# P03_BCS1_USB_Serial_uSD.net
KiCad netlist of a schematic drawn in Altium Designer
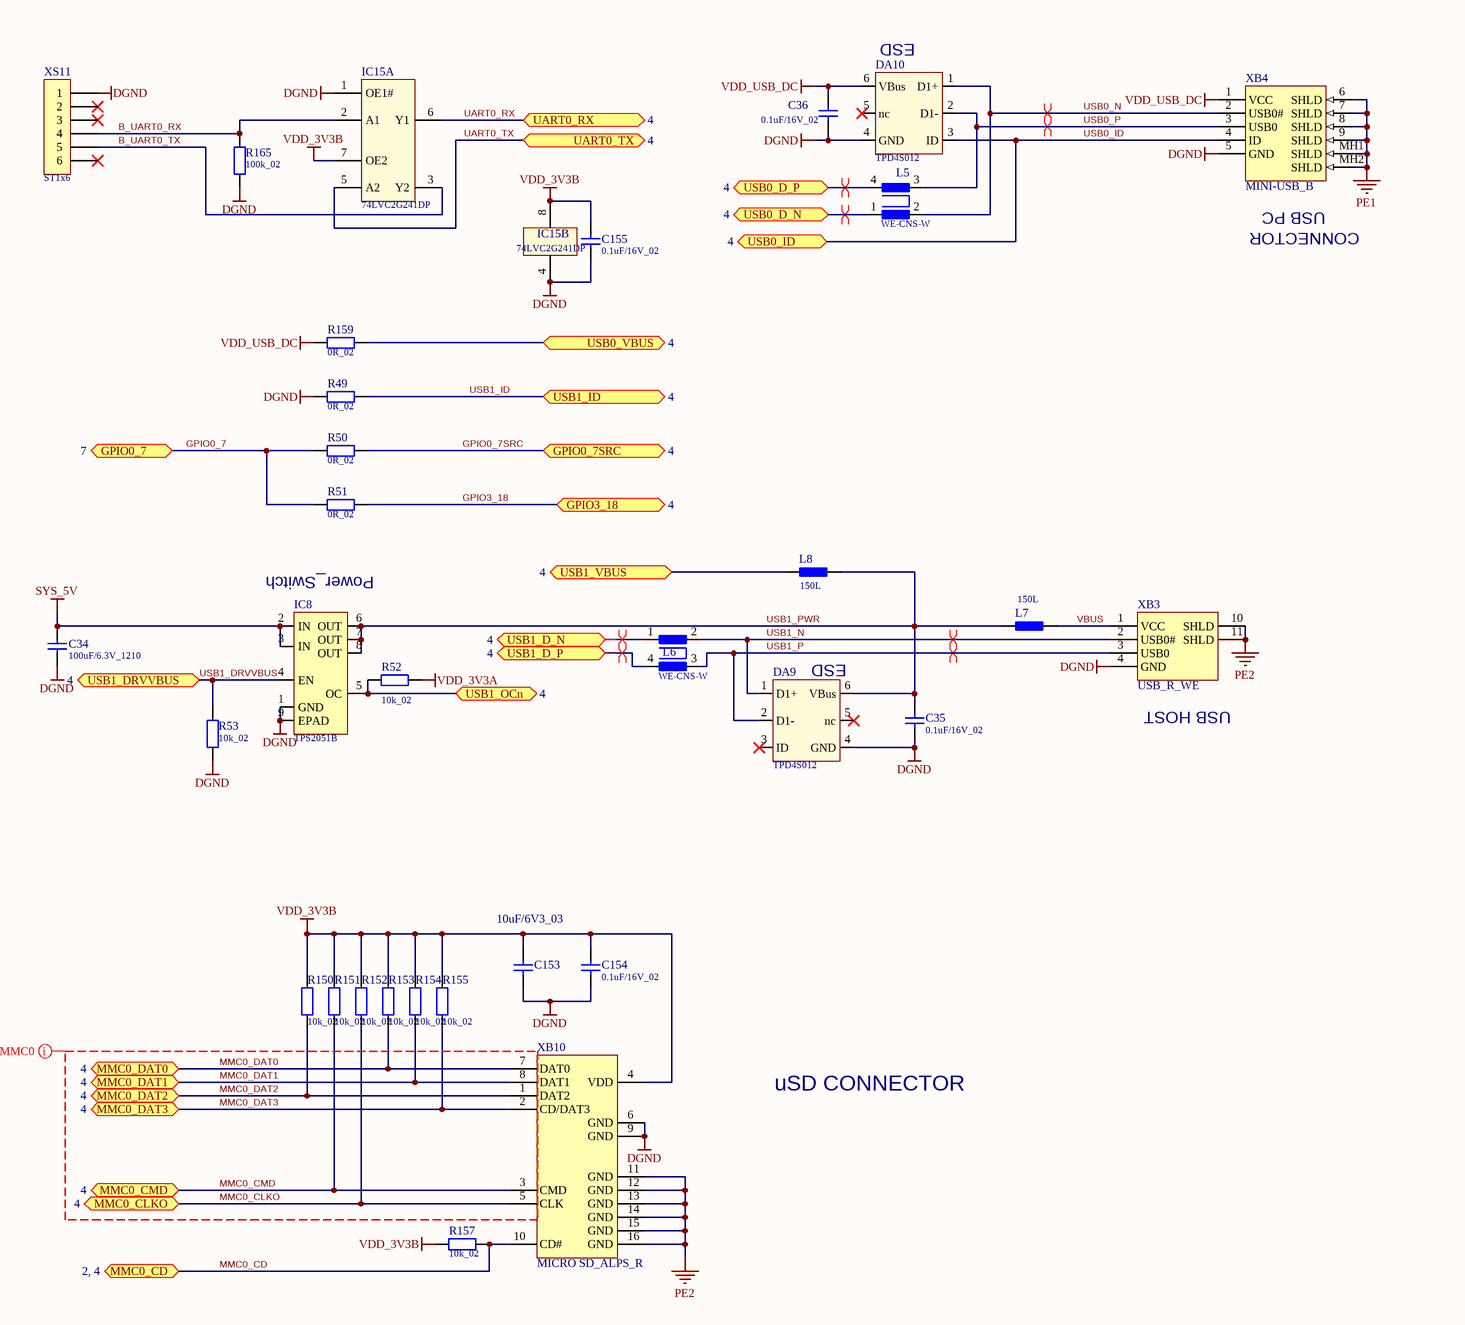
[diagram p0: P03_BCS1_USB, Serial, uSD.SchDoc]

(export (version "E")
  (design (tool "Eeschema 10.0.6"))
  (components
    (comp (ref "C34")
      (value "100uF/6.3V_1210")
      (footprint "CC3225-1210")
      (description "Capacitor 1210; 6.3V")
      (libsource (lib "*") (part "C100uF/6.3V_10"))
    )
    (comp (ref "C35")
      (value "0.1uF/16V_02")
      (footprint "CC1005-0402")
      (description "Capacitor 0402 16V Y5V")
      (libsource (lib "*") (part "C0.1uF/16V_02"))
    )
    (comp (ref "C36")
      (value "0.1uF/16V_02")
      (footprint "CC1005-0402")
      (description "Capacitor 0402 16V Y5V")
      (libsource (lib "*") (part "C0.1uF/16V_02"))
    )
    (comp (ref "C153")
      (value "10uF/6V3_03")
      (footprint "CC1608-0603")
      (description "Capacitor 0603 6V3; 10%, X5R")
      (libsource (lib "*") (part "C10uF/6V3_03"))
    )
    (comp (ref "C154")
      (value "0.1uF/16V_02")
      (footprint "CC1005-0402")
      (description "Capacitor 0402 16V Y5V")
      (libsource (lib "*") (part "C0.1uF/16V_02"))
    )
    (comp (ref "C155")
      (value "0.1uF/16V_02")
      (footprint "CC1005-0402")
      (description "Capacitor 0402 16V Y5V")
      (libsource (lib "*") (part "C0.1uF/16V_02"))
    )
    (comp (ref "DA9")
      (value "TPD4S012")
      (footprint "SON6")
      (description "Diode Array TVS,  for USB2.0 TypB; 4fach")
      (libsource (lib "*") (part "DATPD4S012"))
    )
    (comp (ref "DA10")
      (value "TPD4S012")
      (footprint "SON6")
      (description "Diode Array TVS,  for USB2.0 TypB; 4fach")
      (libsource (lib "") (part "DATPD4S012_1"))
    )
    (comp (ref "IC8")
      (value "TPS2051B")
      (footprint "DGN-MSOP8+1")
      (description "Current-Limited PowerSwitch")
      (libsource (lib "*") (part "ICTPS2051B"))
    )
    (comp (ref "IC15")
      (value "74LVC2G241DP")
      (footprint "TSSOP8 - 3x3")
      (description "dual buffer/line driver; 3-state, 5V-tolerant")
      (libsource (lib "*") (part "IC74LVC2G241DP"))
    )
    (comp (ref "L5")
      (value "WE-CNS-W")
      (footprint "WE-CNS_W - 0805")
      (description "Stromkomp. Datenleitungsfilter WE-CNS-W, 90 Ohm")
      (libsource (lib "*") (part "LWE-CNS FILTER"))
    )
    (comp (ref "L6")
      (value "WE-CNS-W")
      (footprint "WE-CNS_W - 0805")
      (description "Stromkomp. Datenleitungsfilter WE-CNS-W, 90 Ohm")
      (libsource (lib "*") (part "LWE-CNS FILTER"))
    )
    (comp (ref "L7")
      (value "150L")
      (footprint "CR2012-0805")
      (description "Inductor 120 Ohm Ferrite 0805, 800mA")
      (libsource (lib "*") (part "L150 Ohm Ferrite"))
    )
    (comp (ref "L8")
      (value "150L")
      (footprint "CR2012-0805")
      (description "Inductor 120 Ohm Ferrite 0805, 800mA")
      (libsource (lib "*") (part "L150 Ohm Ferrite"))
    )
    (comp (ref "R49")
      (value "0R_02")
      (footprint "CR1005-0402")
      (description "Resistor 0402")
      (libsource (lib "*") (part "R0R_02"))
    )
    (comp (ref "R50")
      (value "0R_02")
      (footprint "CR1005-0402")
      (description "Resistor 0402")
      (libsource (lib "*") (part "R0R_02"))
    )
    (comp (ref "R51")
      (value "0R_02")
      (footprint "CR1005-0402")
      (description "Resistor 0402")
      (libsource (lib "*") (part "R0R_02"))
    )
    (comp (ref "R52")
      (value "10k_02")
      (footprint "CR1005-0402")
      (description "Resistor 0402")
      (libsource (lib "") (part "R10k_02_1"))
    )
    (comp (ref "R53")
      (value "10k_02")
      (footprint "CR1005-0402")
      (description "Resistor 0402")
      (libsource (lib "") (part "R10k_02_2"))
    )
    (comp (ref "R150")
      (value "10k_02")
      (footprint "CR1005-0402")
      (description "Resistor 0402")
      (libsource (lib "*") (part "R10k_02"))
    )
    (comp (ref "R151")
      (value "10k_02")
      (footprint "CR1005-0402")
      (description "Resistor 0402")
      (libsource (lib "*") (part "R10k_02"))
    )
    (comp (ref "R152")
      (value "10k_02")
      (footprint "CR1005-0402")
      (description "Resistor 0402")
      (libsource (lib "*") (part "R10k_02"))
    )
    (comp (ref "R153")
      (value "10k_02")
      (footprint "CR1005-0402")
      (description "Resistor 0402")
      (libsource (lib "*") (part "R10k_02"))
    )
    (comp (ref "R154")
      (value "10k_02")
      (footprint "CR1005-0402")
      (description "Resistor 0402")
      (libsource (lib "*") (part "R10k_02"))
    )
    (comp (ref "R155")
      (value "10k_02")
      (footprint "CR1005-0402")
      (description "Resistor 0402")
      (libsource (lib "*") (part "R10k_02"))
    )
    (comp (ref "R157")
      (value "10k_02")
      (footprint "CR1005-0402")
      (description "Resistor 0402")
      (libsource (lib "") (part "R10k_02_1"))
    )
    (comp (ref "R159")
      (value "0R_02")
      (footprint "CR1005-0402")
      (description "Resistor 0402")
      (libsource (lib "*") (part "R0R_02"))
    )
    (comp (ref "R165")
      (value "100k_02")
      (footprint "CR1005-0402")
      (description "Resistor 0402")
      (libsource (lib "*") (part "R100k_02"))
    )
    (comp (ref "XB3")
      (value "USB_R_WE")
      (footprint "61400416021")
      (description "USB einfach RA Type A")
      (libsource (lib "*") (part "XBUSB_R_WE"))
    )
    (comp (ref "XB4")
      (value "MINI-USB_B")
      (footprint "USB-MINI-B")
      (description "USB MINI Typ B einfach 5pol.")
      (libsource (lib "*") (part "XBUSB_Mini-B"))
    )
    (comp (ref "XB10")
      (value "MICRO SD_ALPS_R")
      (footprint "Micro-SD-Card-Conn-ALPS- Reverse Mount")
      (description "MICRO SD Memory card connector push/push  reverse mount ALPS (SCHA5B0200)")
      (libsource (lib "*") (part "XBMICRO_SD_ALPS_R"))
    )
    (comp (ref "XS11")
      (value "ST1x6")
      (footprint "ST6")
      (description "Modul-Stiftleiste 2.54mm pitch einreihig, 6pol.")
      (libsource (lib "*") (part "XST1X6"))
    )
  )
  (nets
    (net (code "1") (name "/B_UART0_RX") (class "Default")
      (node (ref "IC15") (pin "2") (pinfunction "A1_2") (pintype "passive"))
      (node (ref "R165") (pin "2") (pinfunction "2_2") (pintype "passive"))
      (node (ref "XS11") (pin "4") (pinfunction "4_4") (pintype "passive"))
    )
    (net (code "2") (name "/B_UART0_TX") (class "Default")
      (node (ref "IC15") (pin "3") (pinfunction "Y2_3") (pintype "passive"))
      (node (ref "XS11") (pin "5") (pinfunction "5_5") (pintype "passive"))
    )
    (net (code "3") (name "/GPIO0_7") (class "Default")
      (node (ref "R50") (pin "1") (pinfunction "1_1") (pintype "passive"))
      (node (ref "R51") (pin "1") (pinfunction "1_1") (pintype "passive"))
    )
    (net (code "4") (name "/GPIO0_7SRC") (class "Default")
      (node (ref "R50") (pin "2") (pinfunction "2_2") (pintype "passive"))
    )
    (net (code "5") (name "/GPIO3_18") (class "Default")
      (node (ref "R51") (pin "2") (pinfunction "2_2") (pintype "passive"))
    )
    (net (code "6") (name "/MMC0_CD") (class "Default")
      (node (ref "R157") (pin "2") (pinfunction "2_2") (pintype "passive"))
      (node (ref "XB10") (pin "10") (pinfunction "CD#_10") (pintype "passive"))
    )
    (net (code "7") (name "/MMC0_CLKO") (class "Default")
      (node (ref "R152") (pin "2") (pinfunction "2_2") (pintype "passive"))
      (node (ref "XB10") (pin "5") (pinfunction "CLK_5") (pintype "passive"))
    )
    (net (code "8") (name "/MMC0_CMD") (class "Default")
      (node (ref "R151") (pin "2") (pinfunction "2_2") (pintype "passive"))
      (node (ref "XB10") (pin "3") (pinfunction "CMD_3") (pintype "passive"))
    )
    (net (code "9") (name "/MMC0_DAT0") (class "Default")
      (node (ref "R153") (pin "2") (pinfunction "2_2") (pintype "passive"))
      (node (ref "XB10") (pin "7") (pinfunction "DAT0_7") (pintype "passive"))
    )
    (net (code "10") (name "/MMC0_DAT1") (class "Default")
      (node (ref "R154") (pin "2") (pinfunction "2_2") (pintype "passive"))
      (node (ref "XB10") (pin "8") (pinfunction "DAT1_8") (pintype "passive"))
    )
    (net (code "11") (name "/MMC0_DAT2") (class "Default")
      (node (ref "R150") (pin "2") (pinfunction "2_2") (pintype "passive"))
      (node (ref "XB10") (pin "1") (pinfunction "DAT2_1") (pintype "passive"))
    )
    (net (code "12") (name "/MMC0_DAT3") (class "Default")
      (node (ref "R155") (pin "2") (pinfunction "2_2") (pintype "passive"))
      (node (ref "XB10") (pin "2") (pinfunction "CD/DAT3_2") (pintype "passive"))
    )
    (net (code "13") (name "/UART0_RX") (class "Default")
      (node (ref "IC15") (pin "6") (pinfunction "Y1_6") (pintype "passive"))
    )
    (net (code "14") (name "/UART0_TX") (class "Default")
      (node (ref "IC15") (pin "5") (pinfunction "A2_5") (pintype "passive"))
    )
    (net (code "15") (name "/USB0_D_N") (class "Default")
      (node (ref "L5") (pin "1") (pinfunction "1_1") (pintype "passive"))
    )
    (net (code "16") (name "/USB0_D_P") (class "Default")
      (node (ref "L5") (pin "4") (pinfunction "4_4") (pintype "passive"))
    )
    (net (code "17") (name "/USB0_ID") (class "Default")
      (node (ref "DA10") (pin "3") (pinfunction "ID_3") (pintype "passive"))
      (node (ref "XB4") (pin "4") (pinfunction "ID_4") (pintype "passive"))
    )
    (net (code "18") (name "/USB0_N") (class "Default")
      (node (ref "DA10") (pin "1") (pinfunction "D1+_1") (pintype "passive"))
      (node (ref "L5") (pin "2") (pinfunction "2_2") (pintype "passive"))
      (node (ref "XB4") (pin "2") (pinfunction "USB0#_2") (pintype "passive"))
    )
    (net (code "19") (name "/USB0_P") (class "Default")
      (node (ref "DA10") (pin "2") (pinfunction "D1-_2") (pintype "passive"))
      (node (ref "L5") (pin "3") (pinfunction "3_3") (pintype "passive"))
      (node (ref "XB4") (pin "3") (pinfunction "USB0_3") (pintype "passive"))
    )
    (net (code "20") (name "/USB0_VBUS") (class "Default")
      (node (ref "R159") (pin "2") (pinfunction "2_2") (pintype "passive"))
    )
    (net (code "21") (name "/USB1_DRVVBUS") (class "Default")
      (node (ref "IC8") (pin "4") (pinfunction "EN_4") (pintype "passive"))
      (node (ref "R53") (pin "2") (pinfunction "2_2") (pintype "passive"))
    )
    (net (code "22") (name "/USB1_D_N") (class "Default")
      (node (ref "L6") (pin "1") (pinfunction "1_1") (pintype "passive"))
    )
    (net (code "23") (name "/USB1_D_P") (class "Default")
      (node (ref "L6") (pin "4") (pinfunction "4_4") (pintype "passive"))
    )
    (net (code "24") (name "/USB1_ID") (class "Default")
      (node (ref "R49") (pin "2") (pinfunction "2_2") (pintype "passive"))
    )
    (net (code "25") (name "/USB1_N") (class "Default")
      (node (ref "DA9") (pin "1") (pinfunction "D1+_1") (pintype "passive"))
      (node (ref "L6") (pin "2") (pinfunction "2_2") (pintype "passive"))
      (node (ref "XB3") (pin "2") (pinfunction "USB0#_2") (pintype "passive"))
    )
    (net (code "26") (name "/USB1_OCn") (class "Default")
      (node (ref "IC8") (pin "5") (pinfunction "OC_5") (pintype "power_in"))
      (node (ref "R52") (pin "1") (pinfunction "1_1") (pintype "passive"))
    )
    (net (code "27") (name "/USB1_P") (class "Default")
      (node (ref "DA9") (pin "2") (pinfunction "D1-_2") (pintype "passive"))
      (node (ref "L6") (pin "3") (pinfunction "3_3") (pintype "passive"))
      (node (ref "XB3") (pin "3") (pinfunction "USB0_3") (pintype "passive"))
    )
    (net (code "28") (name "/USB1_PWR") (class "Default")
      (node (ref "C35") (pin "1") (pinfunction "1_1") (pintype "passive"))
      (node (ref "DA9") (pin "6") (pinfunction "VBus_6") (pintype "passive"))
      (node (ref "IC8") (pin "6") (pinfunction "OUT_6") (pintype "passive"))
      (node (ref "IC8") (pin "7") (pinfunction "OUT_7") (pintype "passive"))
      (node (ref "IC8") (pin "8") (pinfunction "OUT_8") (pintype "passive"))
      (node (ref "L7") (pin "1") (pinfunction "1_1") (pintype "passive"))
      (node (ref "L8") (pin "2") (pinfunction "2_2") (pintype "passive"))
    )
    (net (code "29") (name "/USB1_VBUS") (class "Default")
      (node (ref "L8") (pin "1") (pinfunction "1_1") (pintype "passive"))
    )
    (net (code "30") (name "/VBUS") (class "Default")
      (node (ref "L7") (pin "2") (pinfunction "2_2") (pintype "passive"))
      (node (ref "XB3") (pin "1") (pinfunction "VCC_1") (pintype "passive"))
    )
    (net (code "31") (name "DGND") (class "Default")
      (node (ref "C153") (pin "1") (pinfunction "1_1") (pintype "passive"))
      (node (ref "C154") (pin "1") (pinfunction "1_1") (pintype "passive"))
      (node (ref "C155") (pin "2") (pinfunction "2_2") (pintype "passive"))
      (node (ref "C34") (pin "1") (pinfunction "1_1") (pintype "passive"))
      (node (ref "C35") (pin "2") (pinfunction "2_2") (pintype "passive"))
      (node (ref "C36") (pin "2") (pinfunction "2_2") (pintype "passive"))
      (node (ref "DA10") (pin "4") (pinfunction "GND_4") (pintype "passive"))
      (node (ref "DA9") (pin "4") (pinfunction "GND_4") (pintype "passive"))
      (node (ref "IC15") (pin "1") (pinfunction "OE1#_1") (pintype "passive"))
      (node (ref "IC15") (pin "4") (pinfunction "GND_4") (pintype "passive"))
      (node (ref "IC8") (pin "1") (pinfunction "GND_1") (pintype "passive"))
      (node (ref "IC8") (pin "9") (pinfunction "EPAD_9") (pintype "passive"))
      (node (ref "R165") (pin "1") (pinfunction "1_1") (pintype "passive"))
      (node (ref "R49") (pin "1") (pinfunction "1_1") (pintype "passive"))
      (node (ref "R53") (pin "1") (pinfunction "1_1") (pintype "passive"))
      (node (ref "XB10") (pin "6") (pinfunction "GND_6") (pintype "passive"))
      (node (ref "XB10") (pin "9") (pinfunction "GND_9") (pintype "passive"))
      (node (ref "XB3") (pin "4") (pinfunction "GND_4") (pintype "passive"))
      (node (ref "XB4") (pin "5") (pinfunction "GND_5") (pintype "passive"))
      (node (ref "XS11") (pin "1") (pinfunction "1_1") (pintype "passive"))
    )
    (net (code "32") (name "PE1") (class "Default")
      (node (ref "XB4") (pin "6") (pinfunction "SHLD_6") (pintype "input"))
      (node (ref "XB4") (pin "7") (pinfunction "SHLD_7") (pintype "input"))
      (node (ref "XB4") (pin "8") (pinfunction "SHLD_8") (pintype "input"))
      (node (ref "XB4") (pin "9") (pinfunction "SHLD_9") (pintype "input"))
      (node (ref "XB4") (pin "MH1") (pinfunction "SHLD_MH1") (pintype "input"))
      (node (ref "XB4") (pin "MH2") (pinfunction "SHLD_MH2") (pintype "input"))
    )
    (net (code "33") (name "PE2") (class "Default")
      (node (ref "XB10") (pin "11") (pinfunction "GND_11") (pintype "passive"))
      (node (ref "XB10") (pin "12") (pinfunction "GND_12") (pintype "passive"))
      (node (ref "XB10") (pin "13") (pinfunction "GND_13") (pintype "passive"))
      (node (ref "XB10") (pin "14") (pinfunction "GND_14") (pintype "passive"))
      (node (ref "XB10") (pin "15") (pinfunction "GND_15") (pintype "passive"))
      (node (ref "XB10") (pin "16") (pinfunction "GND_16") (pintype "passive"))
      (node (ref "XB3") (pin "10") (pinfunction "SHLD_10") (pintype "passive"))
      (node (ref "XB3") (pin "11") (pinfunction "SHLD_11") (pintype "passive"))
    )
    (net (code "34") (name "SYS_5V") (class "Default")
      (node (ref "C34") (pin "2") (pinfunction "2_2") (pintype "passive"))
      (node (ref "IC8") (pin "2") (pinfunction "IN_2") (pintype "power_in"))
      (node (ref "IC8") (pin "3") (pinfunction "IN_3") (pintype "passive"))
    )
    (net (code "35") (name "VDD_3V3A") (class "Default")
      (node (ref "R52") (pin "2") (pinfunction "2_2") (pintype "passive"))
    )
    (net (code "36") (name "VDD_3V3B") (class "Default")
      (node (ref "C153") (pin "2") (pinfunction "2_2") (pintype "passive"))
      (node (ref "C154") (pin "2") (pinfunction "2_2") (pintype "passive"))
      (node (ref "C155") (pin "1") (pinfunction "1_1") (pintype "passive"))
      (node (ref "IC15") (pin "7") (pinfunction "OE2_7") (pintype "passive"))
      (node (ref "IC15") (pin "8") (pinfunction "VDD_8") (pintype "passive"))
      (node (ref "R150") (pin "1") (pinfunction "1_1") (pintype "passive"))
      (node (ref "R151") (pin "1") (pinfunction "1_1") (pintype "passive"))
      (node (ref "R152") (pin "1") (pinfunction "1_1") (pintype "passive"))
      (node (ref "R153") (pin "1") (pinfunction "1_1") (pintype "passive"))
      (node (ref "R154") (pin "1") (pinfunction "1_1") (pintype "passive"))
      (node (ref "R155") (pin "1") (pinfunction "1_1") (pintype "passive"))
      (node (ref "R157") (pin "1") (pinfunction "1_1") (pintype "passive"))
      (node (ref "XB10") (pin "4") (pinfunction "VDD_4") (pintype "passive"))
    )
    (net (code "37") (name "VDD_USB_DC") (class "Default")
      (node (ref "C36") (pin "1") (pinfunction "1_1") (pintype "passive"))
      (node (ref "DA10") (pin "6") (pinfunction "VBus_6") (pintype "passive"))
      (node (ref "R159") (pin "1") (pinfunction "1_1") (pintype "passive"))
      (node (ref "XB4") (pin "1") (pinfunction "VCC_1") (pintype "passive"))
    )
    (net (code "38") (name "unconnected-(DA9-ID-Pad3)") (class "Default")
      (node (ref "DA9") (pin "3") (pinfunction "ID_3") (pintype "passive+no_connect"))
    )
    (net (code "39") (name "unconnected-(DA9-nc-Pad5)") (class "Default")
      (node (ref "DA9") (pin "5") (pinfunction "nc_5") (pintype "passive+no_connect"))
    )
    (net (code "40") (name "unconnected-(DA10-nc-Pad5)") (class "Default")
      (node (ref "DA10") (pin "5") (pinfunction "nc_5") (pintype "passive+no_connect"))
    )
    (net (code "41") (name "unconnected-(XS11-Pad2)") (class "Default")
      (node (ref "XS11") (pin "2") (pinfunction "2_2") (pintype "passive+no_connect"))
    )
    (net (code "42") (name "unconnected-(XS11-Pad3)") (class "Default")
      (node (ref "XS11") (pin "3") (pinfunction "3_3") (pintype "passive+no_connect"))
    )
    (net (code "43") (name "unconnected-(XS11-Pad6)") (class "Default")
      (node (ref "XS11") (pin "6") (pinfunction "6_6") (pintype "passive+no_connect"))
    )
  )
)
